# alte_schaltung_nicer2.net
KiCad netlist of a schematic drawn in EAGLE
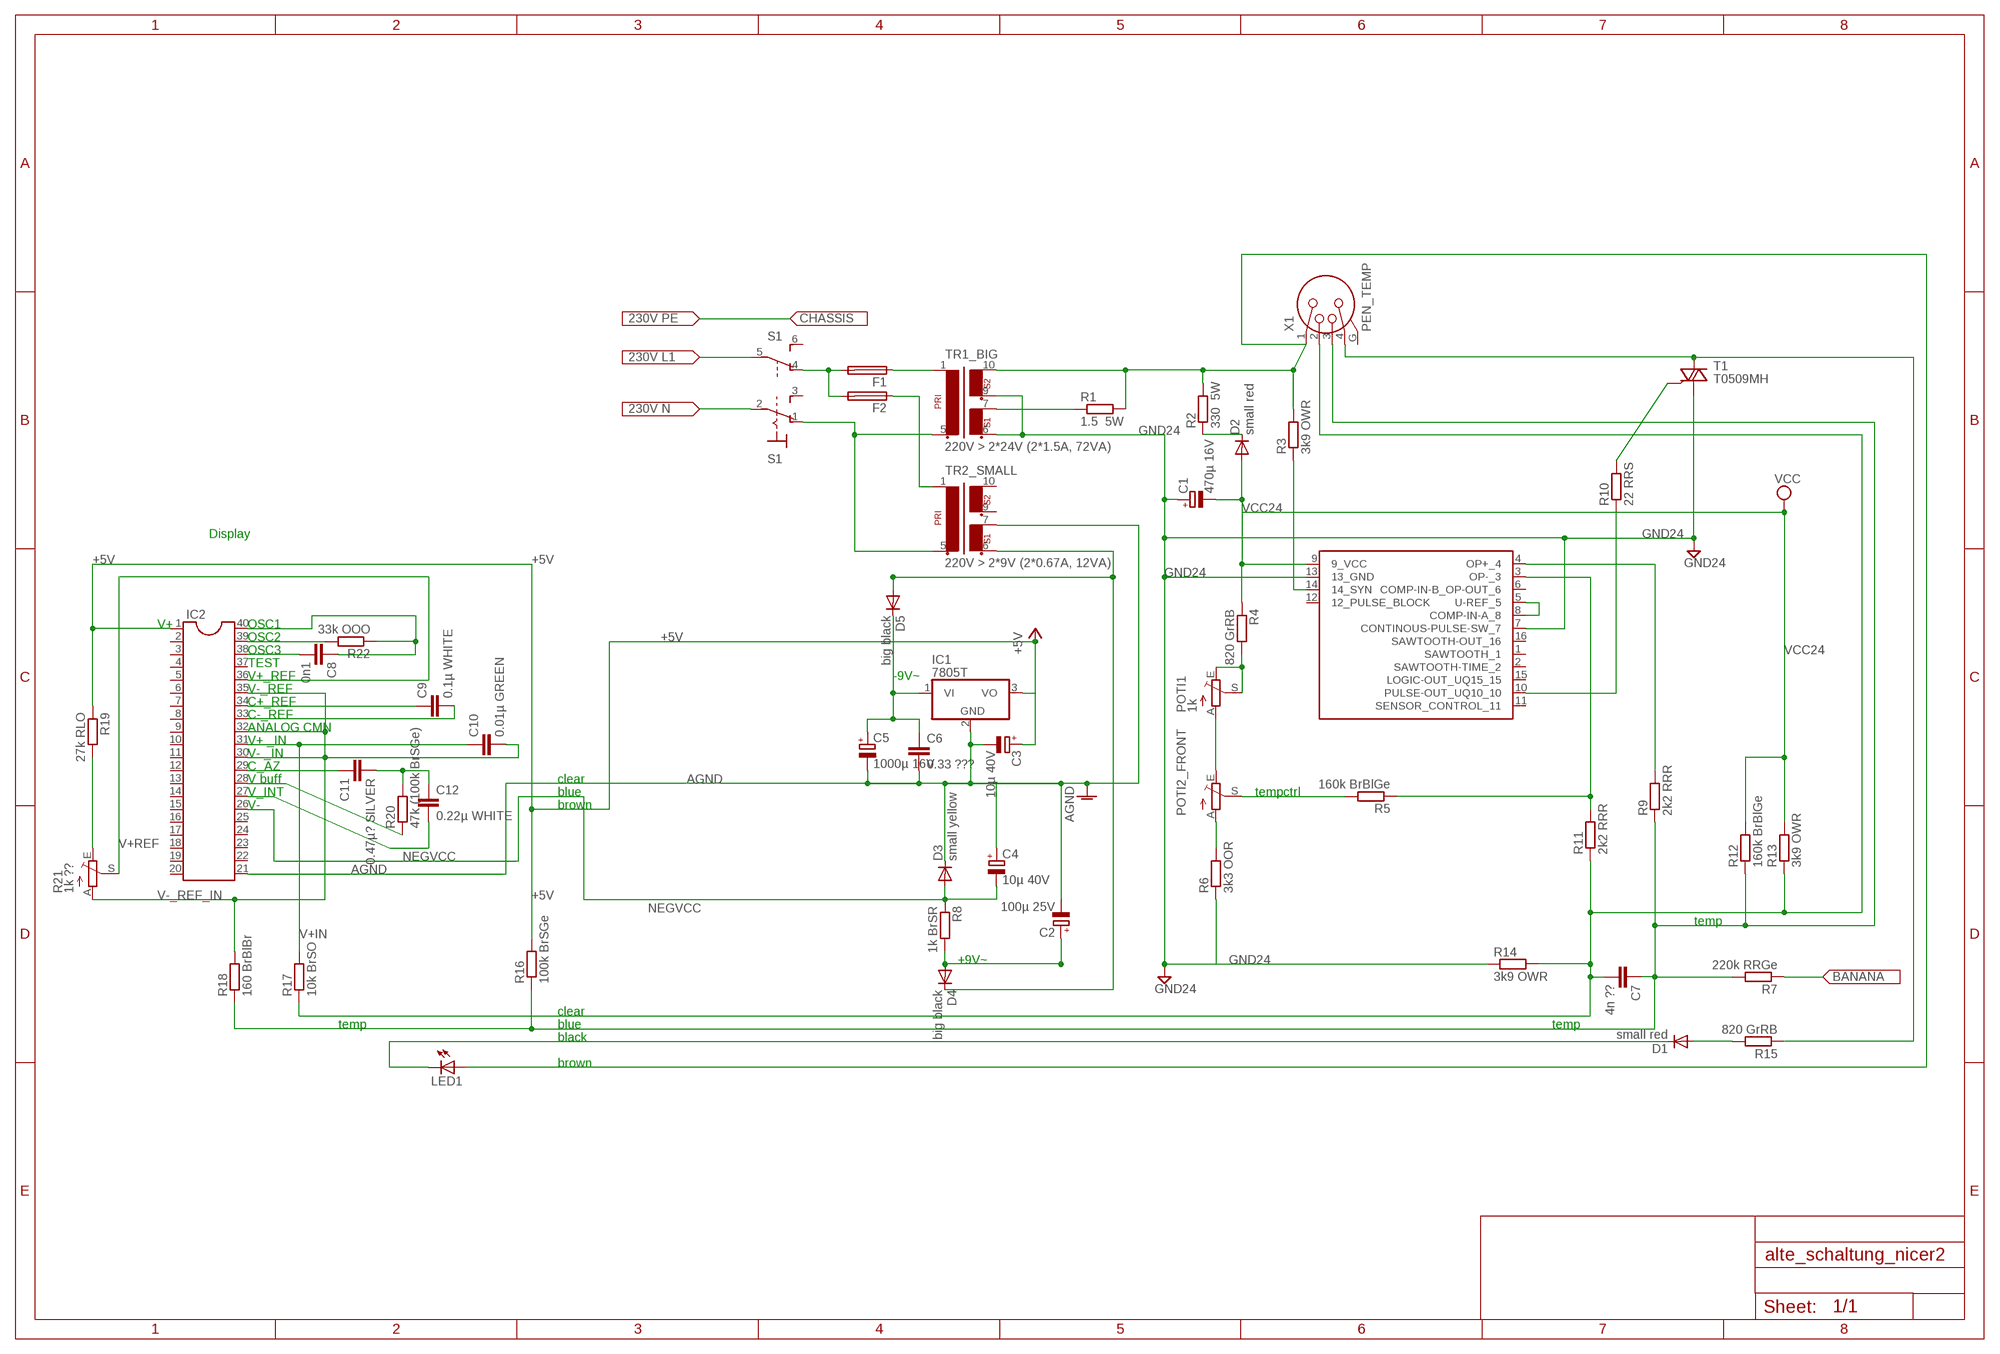
[diagram p0: schematic, sheet 1]

(export (version "E")
  (design (tool "Eeschema 10.0.6"))
  (components
    (comp (ref "C1")
      (value "470µ 16V")
      (footprint "eagle-import:E5-10,5")
      (libsource (lib "eagle-import") (part "CPOL-EUE5-10.5"))
    )
    (comp (ref "C2")
      (value "100µ 25V")
      (footprint "eagle-import:E5-10,5")
      (libsource (lib "eagle-import") (part "CPOL-EUE5-10.5"))
    )
    (comp (ref "C3")
      (value "10µ 40V")
      (footprint "eagle-import:E5-10,5")
      (libsource (lib "eagle-import") (part "CPOL-EUE5-10.5"))
    )
    (comp (ref "C4")
      (value "10µ 40V")
      (footprint "eagle-import:E5-10,5")
      (libsource (lib "eagle-import") (part "CPOL-EUE5-10.5"))
    )
    (comp (ref "C5")
      (value "1000µ 16V")
      (footprint "eagle-import:E5-10,5")
      (libsource (lib "eagle-import") (part "CPOL-EUE5-10.5"))
    )
    (comp (ref "C6")
      (value "0.33 ???")
      (footprint "eagle-import:C075-042X103")
      (libsource (lib "eagle-import") (part "C-EU075-042X103"))
    )
    (comp (ref "C7")
      (value "4n ??")
      (footprint "eagle-import:C050-024X044")
      (libsource (lib "eagle-import") (part "C-EU050-024X044"))
    )
    (comp (ref "C8")
      (value "0n1")
      (footprint "eagle-import:C050-024X044")
      (libsource (lib "eagle-import") (part "C-EU050-024X044"))
    )
    (comp (ref "C9")
      (value "0.1µ WHITE")
      (footprint "eagle-import:C102-043X133")
      (libsource (lib "eagle-import") (part "C-EU102-043X133"))
    )
    (comp (ref "C10")
      (value "0.01µ GREEN")
      (footprint "eagle-import:C102-043X133")
      (libsource (lib "eagle-import") (part "C-EU102-043X133"))
    )
    (comp (ref "C11")
      (value "0.47µ? SILVER")
      (footprint "eagle-import:C102-043X133")
      (libsource (lib "eagle-import") (part "C-EU102-043X133"))
    )
    (comp (ref "C12")
      (value "0.22µ WHITE")
      (footprint "eagle-import:C102-043X133")
      (libsource (lib "eagle-import") (part "C-EU102-043X133"))
    )
    (comp (ref "D1")
      (value "small red")
      (footprint "eagle-import:DO41-10")
      (libsource (lib "eagle-import") (part "1N4004"))
    )
    (comp (ref "D2")
      (value "small red")
      (footprint "eagle-import:DO41-10")
      (libsource (lib "eagle-import") (part "1N4004"))
    )
    (comp (ref "D3")
      (value "small yellow")
      (footprint "eagle-import:DO35-10")
      (libsource (lib "eagle-import") (part "1N4446"))
    )
    (comp (ref "D4")
      (value "big black")
      (footprint "eagle-import:DO41-10")
      (libsource (lib "eagle-import") (part "1N4942"))
    )
    (comp (ref "D5")
      (value "big black")
      (footprint "eagle-import:DO41-10")
      (libsource (lib "eagle-import") (part "1N4942"))
    )
    (comp (ref "F1")
      (value "SH25")
      (footprint "eagle-import:SH25")
      (fields (field (name "MF") "SCHURTER") (field (name "MPN") "0031.8211"))
      (libsource (lib "eagle-import") (part "SH25"))
    )
    (comp (ref "F2")
      (value "SH25")
      (footprint "eagle-import:SH25")
      (fields (field (name "MF") "SCHURTER") (field (name "MPN") "0031.8211"))
      (libsource (lib "eagle-import") (part "SH25"))
    )
    (comp (ref "IC1")
      (value "7805T")
      (footprint "eagle-import:TO220H")
      (libsource (lib "eagle-import") (part "78T05"))
    )
    (comp (ref "IC2")
      (value "DIL40")
      (footprint "eagle-import:DIL40")
      (libsource (lib "eagle-import") (part "DIL40"))
    )
    (comp (ref "LED1")
      (value "LED3MM")
      (footprint "eagle-import:LED3MM")
      (libsource (lib "eagle-import") (part "LED3MM"))
    )
    (comp (ref "POTI1")
      (value "1k")
      (footprint "eagle-import:LI10")
      (libsource (lib "eagle-import") (part "TRIM_EU-LI10"))
    )
    (comp (ref "POTI2_FRONT")
      (value "TRIM_EU-RJ9W")
      (footprint "eagle-import:RJ9W")
      (libsource (lib "eagle-import") (part "TRIM_EU-RJ9W"))
    )
    (comp (ref "R1")
      (value "1.5 5W")
      (footprint "eagle-import:0922_22")
      (libsource (lib "eagle-import") (part "R-EU_0922/22"))
    )
    (comp (ref "R2")
      (value "330 5W")
      (footprint "eagle-import:0922_22")
      (libsource (lib "eagle-import") (part "R-EU_0922/22"))
    )
    (comp (ref "R3")
      (value "3k9 OWR")
      (footprint "eagle-import:0207_12")
      (libsource (lib "eagle-import") (part "R-EU_0207/12"))
    )
    (comp (ref "R4")
      (value "820 GrRB")
      (footprint "eagle-import:0207_12")
      (libsource (lib "eagle-import") (part "R-EU_0207/12"))
    )
    (comp (ref "R5")
      (value "160k BrBlGe")
      (footprint "eagle-import:0207_12")
      (libsource (lib "eagle-import") (part "R-EU_0207/12"))
    )
    (comp (ref "R6")
      (value "3k3 OOR")
      (footprint "eagle-import:0207_12")
      (libsource (lib "eagle-import") (part "R-EU_0207/12"))
    )
    (comp (ref "R7")
      (value "220k RRGe")
      (footprint "eagle-import:0207_12")
      (libsource (lib "eagle-import") (part "R-EU_0207/12"))
    )
    (comp (ref "R8")
      (value "1k BrSR")
      (footprint "eagle-import:0207_12")
      (libsource (lib "eagle-import") (part "R-EU_0207/12"))
    )
    (comp (ref "R9")
      (value "2k2 RRR")
      (footprint "eagle-import:0207_12")
      (libsource (lib "eagle-import") (part "R-EU_0207/12"))
    )
    (comp (ref "R10")
      (value "22 RRS")
      (footprint "eagle-import:0207_12")
      (libsource (lib "eagle-import") (part "R-EU_0207/12"))
    )
    (comp (ref "R11")
      (value "2k2 RRR")
      (footprint "eagle-import:0207_12")
      (libsource (lib "eagle-import") (part "R-EU_0207/12"))
    )
    (comp (ref "R12")
      (value "160k BrBlGe")
      (footprint "eagle-import:0207_12")
      (libsource (lib "eagle-import") (part "R-EU_0207/12"))
    )
    (comp (ref "R13")
      (value "3k9 OWR")
      (footprint "eagle-import:0207_12")
      (libsource (lib "eagle-import") (part "R-EU_0207/12"))
    )
    (comp (ref "R14")
      (value "3k9 OWR")
      (footprint "eagle-import:0207_12")
      (libsource (lib "eagle-import") (part "R-EU_0207/12"))
    )
    (comp (ref "R15")
      (value "820 GrRB")
      (footprint "eagle-import:0207_12")
      (libsource (lib "eagle-import") (part "R-EU_0207/12"))
    )
    (comp (ref "R16")
      (value "100k BrSGe")
      (footprint "eagle-import:0207_12")
      (libsource (lib "eagle-import") (part "R-EU_0207/12"))
    )
    (comp (ref "R17")
      (value "10k BrSO")
      (footprint "eagle-import:0207_12")
      (libsource (lib "eagle-import") (part "R-EU_0207/12"))
    )
    (comp (ref "R18")
      (value "160 BrBlBr")
      (footprint "eagle-import:0207_12")
      (libsource (lib "eagle-import") (part "R-EU_0207/12"))
    )
    (comp (ref "R19")
      (value "27k RLO")
      (footprint "eagle-import:0207_12")
      (libsource (lib "eagle-import") (part "R-EU_0207/12"))
    )
    (comp (ref "R20")
      (value "47k (100k BrSGe)")
      (footprint "eagle-import:0207_12")
      (libsource (lib "eagle-import") (part "R-EU_0207/12"))
    )
    (comp (ref "R21")
      (value "1k ??")
      (footprint "eagle-import:SP19L")
      (libsource (lib "eagle-import") (part "TRIM_EU-B90P"))
    )
    (comp (ref "R22")
      (value "33k OOO")
      (footprint "eagle-import:0207_12")
      (libsource (lib "eagle-import") (part "R-EU_0207/12"))
    )
    (comp (ref "S1")
      (value "320-938")
      (footprint "eagle-import:320-938")
      (libsource (lib "eagle-import") (part "320-938"))
    )
    (comp (ref "T1")
      (value "T0509MH")
      (footprint "eagle-import:TO220AB")
      (libsource (lib "eagle-import") (part "BT136"))
    )
    (comp (ref "TR1_BIG")
      (value "220V > 2*24V (2*1.5A, 72VA)")
      (footprint "eagle-import:EI42-2")
      (libsource (lib "eagle-import") (part "EI42-2"))
    )
    (comp (ref "TR2_SMALL")
      (value "220V > 2*9V (2*0.67A, 12VA)")
      (footprint "eagle-import:EI42-2")
      (libsource (lib "eagle-import") (part "EI42-2"))
    )
    (comp (ref "U$1")
      (value "U106BS-DIL16")
      (footprint "eagle-import:DIL16")
      (libsource (lib "eagle-import") (part "U106BS-DIL16"))
    )
    (comp (ref "X1")
      (value "PEN_TEMP")
      (footprint "eagle-import:NC4FBV")
      (fields (field (name "MPN") "NC4FBV"))
      (libsource (lib "eagle-import") (part "NC4FBV"))
    )
  )
  (nets
    (net (code "1") (name "+5V") (class "Default")
      (node (ref "C3") (pin "+") (pinfunction "+_+") (pintype "passive"))
      (node (ref "IC1") (pin "3") (pinfunction "VO_3") (pintype "passive"))
      (node (ref "IC2") (pin "1") (pinfunction "1_1") (pintype "passive"))
      (node (ref "R16") (pin "2") (pinfunction "2_2") (pintype "passive"))
      (node (ref "R19") (pin "1") (pinfunction "1_1") (pintype "passive"))
    )
    (net (code "2") (name "/NEGVCC") (class "Default")
      (node (ref "C4") (pin "-") (pinfunction "-_-") (pintype "passive"))
      (node (ref "D3") (pin "A") (pinfunction "A_A") (pintype "passive"))
      (node (ref "IC2") (pin "26") (pinfunction "26_26") (pintype "passive"))
      (node (ref "R8") (pin "1") (pinfunction "1_1") (pintype "passive"))
    )
    (net (code "3") (name "/V+IN") (class "Default")
      (node (ref "C10") (pin "1") (pinfunction "1_1") (pintype "passive"))
      (node (ref "IC2") (pin "31") (pinfunction "31_31") (pintype "passive"))
      (node (ref "R17") (pin "2") (pinfunction "2_2") (pintype "passive"))
    )
    (net (code "4") (name "/V+REF") (class "Default")
      (node (ref "IC2") (pin "36") (pinfunction "36_36") (pintype "passive"))
      (node (ref "R21") (pin "S") (pinfunction "S_S") (pintype "passive"))
    )
    (net (code "5") (name "/V-_REF_IN") (class "Default")
      (node (ref "C10") (pin "2") (pinfunction "2_2") (pintype "passive"))
      (node (ref "IC2") (pin "30") (pinfunction "30_30") (pintype "passive"))
      (node (ref "IC2") (pin "32") (pinfunction "32_32") (pintype "passive"))
      (node (ref "IC2") (pin "35") (pinfunction "35_35") (pintype "passive"))
      (node (ref "R18") (pin "2") (pinfunction "2_2") (pintype "passive"))
      (node (ref "R21") (pin "A") (pinfunction "A_A") (pintype "passive"))
    )
    (net (code "6") (name "AGND") (class "Default")
      (node (ref "C2") (pin "-") (pinfunction "-_-") (pintype "passive"))
      (node (ref "C3") (pin "-") (pinfunction "-_-") (pintype "passive"))
      (node (ref "C4") (pin "+") (pinfunction "+_+") (pintype "passive"))
      (node (ref "C5") (pin "-") (pinfunction "-_-") (pintype "passive"))
      (node (ref "C6") (pin "2") (pinfunction "2_2") (pintype "passive"))
      (node (ref "D3") (pin "C") (pinfunction "C_C") (pintype "passive"))
      (node (ref "IC1") (pin "2") (pinfunction "GND_2") (pintype "passive"))
      (node (ref "IC2") (pin "21") (pinfunction "21_21") (pintype "passive"))
      (node (ref "TR2_SMALL") (pin "7") (pinfunction "4_7") (pintype "passive"))
    )
    (net (code "7") (name "GND24") (class "Default")
      (node (ref "C1") (pin "+") (pinfunction "+_+") (pintype "passive"))
      (node (ref "R14") (pin "1") (pinfunction "1_1") (pintype "passive"))
      (node (ref "R6") (pin "1") (pinfunction "1_1") (pintype "passive"))
      (node (ref "T1") (pin "1") (pinfunction "A1_1") (pintype "passive"))
      (node (ref "TR1_BIG") (pin "6") (pinfunction "3_6") (pintype "passive"))
      (node (ref "TR1_BIG") (pin "9") (pinfunction "5_9") (pintype "passive"))
      (node (ref "U$1") (pin "13") (pinfunction "13_GND_13") (pintype "power_in"))
      (node (ref "U$1") (pin "7") (pinfunction "CONTINOUS-PULSE-SW_7_7") (pintype "input"))
    )
    (net (code "8") (name "Net-(C2-Pad+)") (class "Default")
      (node (ref "C2") (pin "+") (pinfunction "+_+") (pintype "passive"))
      (node (ref "D4") (pin "A") (pinfunction "A_A") (pintype "passive"))
      (node (ref "R8") (pin "2") (pinfunction "2_2") (pintype "passive"))
    )
    (net (code "9") (name "Net-(C7-Pad1)") (class "Default")
      (node (ref "C7") (pin "1") (pinfunction "1_1") (pintype "passive"))
      (node (ref "R12") (pin "1") (pinfunction "1_1") (pintype "passive"))
      (node (ref "R16") (pin "1") (pinfunction "1_1") (pintype "passive"))
      (node (ref "R18") (pin "1") (pinfunction "1_1") (pintype "passive"))
      (node (ref "R7") (pin "2") (pinfunction "2_2") (pintype "passive"))
      (node (ref "R9") (pin "1") (pinfunction "1_1") (pintype "passive"))
      (node (ref "X1") (pin "3") (pinfunction "3_3") (pintype "passive"))
    )
    (net (code "10") (name "Net-(C7-Pad2)") (class "Default")
      (node (ref "C7") (pin "2") (pinfunction "2_2") (pintype "passive"))
      (node (ref "R11") (pin "1") (pinfunction "1_1") (pintype "passive"))
      (node (ref "R13") (pin "1") (pinfunction "1_1") (pintype "passive"))
      (node (ref "R14") (pin "2") (pinfunction "2_2") (pintype "passive"))
      (node (ref "R17") (pin "1") (pinfunction "1_1") (pintype "passive"))
      (node (ref "X1") (pin "2") (pinfunction "2_2") (pintype "passive"))
    )
    (net (code "11") (name "Net-(C8-Pad1)") (class "Default")
      (node (ref "C8") (pin "1") (pinfunction "1_1") (pintype "passive"))
      (node (ref "IC2") (pin "40") (pinfunction "40_40") (pintype "passive"))
      (node (ref "R22") (pin "1") (pinfunction "1_1") (pintype "passive"))
    )
    (net (code "12") (name "Net-(C8-Pad2)") (class "Default")
      (node (ref "C8") (pin "2") (pinfunction "2_2") (pintype "passive"))
      (node (ref "IC2") (pin "38") (pinfunction "38_38") (pintype "passive"))
    )
    (net (code "13") (name "Net-(C9-Pad1)") (class "Default")
      (node (ref "C9") (pin "1") (pinfunction "1_1") (pintype "passive"))
      (node (ref "IC2") (pin "34") (pinfunction "34_34") (pintype "passive"))
    )
    (net (code "14") (name "Net-(C9-Pad2)") (class "Default")
      (node (ref "C9") (pin "2") (pinfunction "2_2") (pintype "passive"))
      (node (ref "IC2") (pin "33") (pinfunction "33_33") (pintype "passive"))
    )
    (net (code "15") (name "Net-(C11-Pad1)") (class "Default")
      (node (ref "C11") (pin "1") (pinfunction "1_1") (pintype "passive"))
      (node (ref "IC2") (pin "29") (pinfunction "29_29") (pintype "passive"))
    )
    (net (code "16") (name "Net-(C11-Pad2)") (class "Default")
      (node (ref "C11") (pin "2") (pinfunction "2_2") (pintype "passive"))
      (node (ref "C12") (pin "1") (pinfunction "1_1") (pintype "passive"))
      (node (ref "R20") (pin "2") (pinfunction "2_2") (pintype "passive"))
    )
    (net (code "17") (name "Net-(C12-Pad2)") (class "Default")
      (node (ref "C12") (pin "2") (pinfunction "2_2") (pintype "passive"))
      (node (ref "IC2") (pin "27") (pinfunction "27_27") (pintype "passive"))
    )
    (net (code "18") (name "Net-(D1-PadA)") (class "Default")
      (node (ref "D1") (pin "A") (pinfunction "A_A") (pintype "passive"))
      (node (ref "R15") (pin "2") (pinfunction "2_2") (pintype "passive"))
    )
    (net (code "19") (name "Net-(D2-PadC)") (class "Default")
      (node (ref "D2") (pin "C") (pinfunction "C_C") (pintype "passive"))
      (node (ref "R2") (pin "1") (pinfunction "1_1") (pintype "passive"))
    )
    (net (code "20") (name "Net-(F1-Pad1)") (class "Default")
      (node (ref "F1") (pin "1") (pinfunction "1_1") (pintype "passive"))
      (node (ref "TR1_BIG") (pin "1") (pinfunction "1_1") (pintype "passive"))
    )
    (net (code "21") (name "Net-(F2-Pad1)") (class "Default")
      (node (ref "F2") (pin "1") (pinfunction "1_1") (pintype "passive"))
      (node (ref "TR2_SMALL") (pin "1") (pinfunction "1_1") (pintype "passive"))
    )
    (net (code "22") (name "Net-(IC1-VI)") (class "Default")
      (node (ref "C5") (pin "+") (pinfunction "+_+") (pintype "passive"))
      (node (ref "C6") (pin "1") (pinfunction "1_1") (pintype "passive"))
      (node (ref "D5") (pin "C") (pinfunction "C_C") (pintype "passive"))
      (node (ref "IC1") (pin "1") (pinfunction "VI_1") (pintype "input"))
    )
    (net (code "23") (name "Net-(IC2-Pad28)") (class "Default")
      (node (ref "IC2") (pin "28") (pinfunction "28_28") (pintype "passive"))
      (node (ref "R20") (pin "1") (pinfunction "1_1") (pintype "passive"))
    )
    (net (code "24") (name "Net-(IC2-Pad39)") (class "Default")
      (node (ref "IC2") (pin "39") (pinfunction "39_39") (pintype "passive"))
      (node (ref "R22") (pin "2") (pinfunction "2_2") (pintype "passive"))
    )
    (net (code "25") (name "Net-(LED1-C)") (class "Default")
      (node (ref "D1") (pin "C") (pinfunction "C_C") (pintype "passive"))
      (node (ref "LED1") (pin "K") (pinfunction "C_K") (pintype "passive"))
    )
    (net (code "26") (name "Net-(POTI1-PadA)") (class "Default")
      (node (ref "POTI1") (pin "A") (pinfunction "A_A") (pintype "passive"))
      (node (ref "POTI2_FRONT") (pin "E") (pinfunction "E_E") (pintype "passive"))
    )
    (net (code "27") (name "Net-(POTI1-PadE)") (class "Default")
      (node (ref "POTI1") (pin "E") (pinfunction "E_E") (pintype "passive"))
      (node (ref "POTI1") (pin "S") (pinfunction "S_S") (pintype "passive"))
      (node (ref "R4") (pin "2") (pinfunction "2_2") (pintype "passive"))
    )
    (net (code "28") (name "Net-(POTI2_FRONT-PadA)") (class "Default")
      (node (ref "POTI2_FRONT") (pin "A") (pinfunction "A_A") (pintype "passive"))
      (node (ref "R6") (pin "2") (pinfunction "2_2") (pintype "passive"))
    )
    (net (code "29") (name "Net-(POTI2_FRONT-PadS)") (class "Default")
      (node (ref "POTI2_FRONT") (pin "S") (pinfunction "S_S") (pintype "passive"))
      (node (ref "R5") (pin "2") (pinfunction "2_2") (pintype "passive"))
    )
    (net (code "30") (name "Net-(R19-Pad2)") (class "Default")
      (node (ref "R19") (pin "2") (pinfunction "2_2") (pintype "passive"))
      (node (ref "R21") (pin "E") (pinfunction "E_E") (pintype "passive"))
    )
    (net (code "31") (name "Net-(S1A-O)") (class "Default")
      (node (ref "S1") (pin "1") (pinfunction "O_1") (pintype "passive"))
      (node (ref "TR1_BIG") (pin "5") (pinfunction "2_5") (pintype "passive"))
      (node (ref "TR2_SMALL") (pin "5") (pinfunction "2_5") (pintype "passive"))
    )
    (net (code "32") (name "Net-(S1B-O)") (class "Default")
      (node (ref "F1") (pin "2") (pinfunction "2_2") (pintype "passive"))
      (node (ref "F2") (pin "2") (pinfunction "2_2") (pintype "passive"))
      (node (ref "S1") (pin "4") (pinfunction "O_4") (pintype "passive"))
    )
    (net (code "33") (name "Net-(T1-A2)") (class "Default")
      (node (ref "R15") (pin "1") (pinfunction "1_1") (pintype "passive"))
      (node (ref "T1") (pin "2") (pinfunction "A2_2") (pintype "passive"))
      (node (ref "X1") (pin "4") (pinfunction "4_4") (pintype "passive"))
    )
    (net (code "34") (name "Net-(T1-G)") (class "Default")
      (node (ref "R10") (pin "2") (pinfunction "2_2") (pintype "passive"))
      (node (ref "T1") (pin "3") (pinfunction "G_3") (pintype "passive"))
    )
    (net (code "35") (name "Net-(TR1_BIG-4)") (class "Default")
      (node (ref "R1") (pin "1") (pinfunction "1_1") (pintype "passive"))
      (node (ref "TR1_BIG") (pin "7") (pinfunction "4_7") (pintype "passive"))
    )
    (net (code "36") (name "Net-(TR1_BIG-6)") (class "Default")
      (node (ref "LED1") (pin "A") (pinfunction "A_A") (pintype "passive"))
      (node (ref "R1") (pin "2") (pinfunction "2_2") (pintype "passive"))
      (node (ref "R2") (pin "2") (pinfunction "2_2") (pintype "passive"))
      (node (ref "R3") (pin "2") (pinfunction "2_2") (pintype "passive"))
      (node (ref "TR1_BIG") (pin "10") (pinfunction "6_10") (pintype "passive"))
      (node (ref "X1") (pin "1") (pinfunction "1_1") (pintype "passive"))
    )
    (net (code "37") (name "Net-(TR2_SMALL-3)") (class "Default")
      (node (ref "D4") (pin "C") (pinfunction "C_C") (pintype "passive"))
      (node (ref "D5") (pin "A") (pinfunction "A_A") (pintype "passive"))
      (node (ref "TR2_SMALL") (pin "6") (pinfunction "3_6") (pintype "passive"))
    )
    (net (code "38") (name "Net-(U$1-14_SYN)") (class "Default")
      (node (ref "R3") (pin "1") (pinfunction "1_1") (pintype "passive"))
      (node (ref "U$1") (pin "14") (pinfunction "14_SYN_14") (pintype "input"))
    )
    (net (code "39") (name "Net-(U$1-COMP-IN-A_8)") (class "Default")
      (node (ref "U$1") (pin "5") (pinfunction "U-REF_5_5") (pintype "input"))
      (node (ref "U$1") (pin "8") (pinfunction "COMP-IN-A_8_8") (pintype "input"))
    )
    (net (code "40") (name "Net-(U$1-OP+_4)") (class "Default")
      (node (ref "R9") (pin "2") (pinfunction "2_2") (pintype "passive"))
      (node (ref "U$1") (pin "4") (pinfunction "OP+_4_4") (pintype "input"))
    )
    (net (code "41") (name "Net-(U$1-OP-_3)") (class "Default")
      (node (ref "R11") (pin "2") (pinfunction "2_2") (pintype "passive"))
      (node (ref "R5") (pin "1") (pinfunction "1_1") (pintype "passive"))
      (node (ref "U$1") (pin "3") (pinfunction "OP-_3_3") (pintype "input"))
    )
    (net (code "42") (name "Net-(U$1-PULSE-OUT_UQ10_10)") (class "Default")
      (node (ref "R10") (pin "1") (pinfunction "1_1") (pintype "passive"))
      (node (ref "U$1") (pin "10") (pinfunction "PULSE-OUT_UQ10_10_10") (pintype "output"))
    )
    (net (code "43") (name "VCC") (class "Default")
      (node (ref "C1") (pin "-") (pinfunction "-_-") (pintype "passive"))
      (node (ref "D2") (pin "A") (pinfunction "A_A") (pintype "passive"))
      (node (ref "R12") (pin "2") (pinfunction "2_2") (pintype "passive"))
      (node (ref "R13") (pin "2") (pinfunction "2_2") (pintype "passive"))
      (node (ref "R4") (pin "1") (pinfunction "1_1") (pintype "passive"))
      (node (ref "U$1") (pin "9") (pinfunction "9_VCC_9") (pintype "power_in"))
    )
    (net (code "44") (name "unconnected-(IC2-Pad2)") (class "Default")
      (node (ref "IC2") (pin "2") (pinfunction "2_2") (pintype "passive"))
    )
    (net (code "45") (name "unconnected-(IC2-Pad3)") (class "Default")
      (node (ref "IC2") (pin "3") (pinfunction "3_3") (pintype "passive"))
    )
    (net (code "46") (name "unconnected-(IC2-Pad4)") (class "Default")
      (node (ref "IC2") (pin "4") (pinfunction "4_4") (pintype "passive"))
    )
    (net (code "47") (name "unconnected-(IC2-Pad5)") (class "Default")
      (node (ref "IC2") (pin "5") (pinfunction "5_5") (pintype "passive"))
    )
    (net (code "48") (name "unconnected-(IC2-Pad6)") (class "Default")
      (node (ref "IC2") (pin "6") (pinfunction "6_6") (pintype "passive"))
    )
    (net (code "49") (name "unconnected-(IC2-Pad7)") (class "Default")
      (node (ref "IC2") (pin "7") (pinfunction "7_7") (pintype "passive"))
    )
    (net (code "50") (name "unconnected-(IC2-Pad8)") (class "Default")
      (node (ref "IC2") (pin "8") (pinfunction "8_8") (pintype "passive"))
    )
    (net (code "51") (name "unconnected-(IC2-Pad9)") (class "Default")
      (node (ref "IC2") (pin "9") (pinfunction "9_9") (pintype "passive"))
    )
    (net (code "52") (name "unconnected-(IC2-Pad10)") (class "Default")
      (node (ref "IC2") (pin "10") (pinfunction "10_10") (pintype "passive"))
    )
    (net (code "53") (name "unconnected-(IC2-Pad11)") (class "Default")
      (node (ref "IC2") (pin "11") (pinfunction "11_11") (pintype "passive"))
    )
    (net (code "54") (name "unconnected-(IC2-Pad12)") (class "Default")
      (node (ref "IC2") (pin "12") (pinfunction "12_12") (pintype "passive"))
    )
    (net (code "55") (name "unconnected-(IC2-Pad13)") (class "Default")
      (node (ref "IC2") (pin "13") (pinfunction "13_13") (pintype "passive"))
    )
    (net (code "56") (name "unconnected-(IC2-Pad14)") (class "Default")
      (node (ref "IC2") (pin "14") (pinfunction "14_14") (pintype "passive"))
    )
    (net (code "57") (name "unconnected-(IC2-Pad15)") (class "Default")
      (node (ref "IC2") (pin "15") (pinfunction "15_15") (pintype "passive"))
    )
    (net (code "58") (name "unconnected-(IC2-Pad16)") (class "Default")
      (node (ref "IC2") (pin "16") (pinfunction "16_16") (pintype "passive"))
    )
    (net (code "59") (name "unconnected-(IC2-Pad17)") (class "Default")
      (node (ref "IC2") (pin "17") (pinfunction "17_17") (pintype "passive"))
    )
    (net (code "60") (name "unconnected-(IC2-Pad18)") (class "Default")
      (node (ref "IC2") (pin "18") (pinfunction "18_18") (pintype "passive"))
    )
    (net (code "61") (name "unconnected-(IC2-Pad19)") (class "Default")
      (node (ref "IC2") (pin "19") (pinfunction "19_19") (pintype "passive"))
    )
    (net (code "62") (name "unconnected-(IC2-Pad20)") (class "Default")
      (node (ref "IC2") (pin "20") (pinfunction "20_20") (pintype "passive"))
    )
    (net (code "63") (name "unconnected-(IC2-Pad22)") (class "Default")
      (node (ref "IC2") (pin "22") (pinfunction "22_22") (pintype "passive"))
    )
    (net (code "64") (name "unconnected-(IC2-Pad23)") (class "Default")
      (node (ref "IC2") (pin "23") (pinfunction "23_23") (pintype "passive"))
    )
    (net (code "65") (name "unconnected-(IC2-Pad24)") (class "Default")
      (node (ref "IC2") (pin "24") (pinfunction "24_24") (pintype "passive"))
    )
    (net (code "66") (name "unconnected-(IC2-Pad25)") (class "Default")
      (node (ref "IC2") (pin "25") (pinfunction "25_25") (pintype "passive"))
    )
    (net (code "67") (name "unconnected-(IC2-Pad37)") (class "Default")
      (node (ref "IC2") (pin "37") (pinfunction "37_37") (pintype "passive"))
    )
    (net (code "68") (name "unconnected-(R7-Pad1)") (class "Default")
      (node (ref "R7") (pin "1") (pinfunction "1_1") (pintype "passive"))
    )
    (net (code "69") (name "unconnected-(S1A-P-Pad2)") (class "Default")
      (node (ref "S1") (pin "2") (pinfunction "P_2") (pintype "passive"))
    )
    (net (code "70") (name "unconnected-(S1A-S-Pad3)") (class "Default")
      (node (ref "S1") (pin "3") (pinfunction "S_3") (pintype "passive"))
    )
    (net (code "71") (name "unconnected-(S1B-P-Pad5)") (class "Default")
      (node (ref "S1") (pin "5") (pinfunction "P_5") (pintype "passive"))
    )
    (net (code "72") (name "unconnected-(S1B-S-Pad6)") (class "Default")
      (node (ref "S1") (pin "6") (pinfunction "S_6") (pintype "passive"))
    )
    (net (code "73") (name "unconnected-(TR2_SMALL-5-Pad9)") (class "Default")
      (node (ref "TR2_SMALL") (pin "9") (pinfunction "5_9") (pintype "passive"))
    )
    (net (code "74") (name "unconnected-(TR2_SMALL-6-Pad10)") (class "Default")
      (node (ref "TR2_SMALL") (pin "10") (pinfunction "6_10") (pintype "passive"))
    )
    (net (code "75") (name "unconnected-(U$1-12_PULSE_BLOCK-Pad12)") (class "Default")
      (node (ref "U$1") (pin "12") (pinfunction "12_PULSE_BLOCK_12") (pintype "input"))
    )
    (net (code "76") (name "unconnected-(U$1-COMP-IN-B_OP-OUT_6-Pad6)") (class "Default")
      (node (ref "U$1") (pin "6") (pinfunction "COMP-IN-B_OP-OUT_6_6") (pintype "output"))
    )
    (net (code "77") (name "unconnected-(U$1-LOGIC-OUT_UQ15_15-Pad15)") (class "Default")
      (node (ref "U$1") (pin "15") (pinfunction "LOGIC-OUT_UQ15_15_15") (pintype "output"))
    )
    (net (code "78") (name "unconnected-(U$1-SAWTOOTH-OUT_16-Pad16)") (class "Default")
      (node (ref "U$1") (pin "16") (pinfunction "SAWTOOTH-OUT_16_16") (pintype "output"))
    )
    (net (code "79") (name "unconnected-(U$1-SAWTOOTH-TIME_2-Pad2)") (class "Default")
      (node (ref "U$1") (pin "2") (pinfunction "SAWTOOTH-TIME_2_2") (pintype "input"))
    )
    (net (code "80") (name "unconnected-(U$1-SAWTOOTH_1-Pad1)") (class "Default")
      (node (ref "U$1") (pin "1") (pinfunction "SAWTOOTH_1_1") (pintype "input"))
    )
    (net (code "81") (name "unconnected-(U$1-SENSOR_CONTROL_11-Pad11)") (class "Default")
      (node (ref "U$1") (pin "11") (pinfunction "SENSOR_CONTROL_11_11") (pintype "input"))
    )
    (net (code "82") (name "unconnected-(X1-PadG)") (class "Default")
      (node (ref "X1") (pin "G") (pinfunction "G_G") (pintype "passive"))
    )
  )
)
